# ir_circuit_rev01.net
KiCad netlist of a schematic drawn in EAGLE
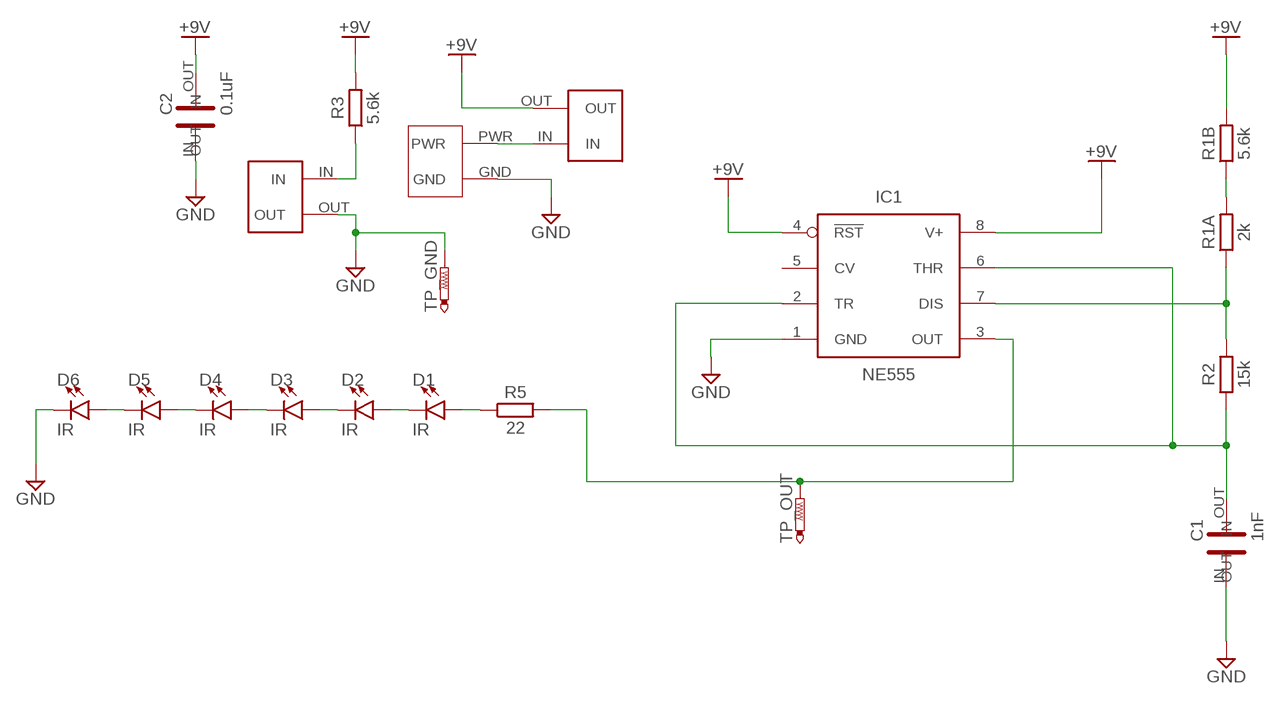
[diagram p0: schematic, sheet 1]

(export (version "E")
  (design (tool "Eeschema 10.0.6"))
  (components
    (comp (ref "BATT")
      (value "JST_THRU_HOLE")
      (footprint "eagle-import:JST_THRU_HOLE")
      (libsource (lib "eagle-import") (part "JST_THRU_HOLE"))
    )
    (comp (ref "C1")
      (value "1nF")
      (footprint "eagle-import:THRU_HOLE_CAP")
      (libsource (lib "eagle-import") (part "THRU_HOLE_CAP"))
    )
    (comp (ref "C2")
      (value "0.1uF")
      (footprint "eagle-import:THRU_HOLE_CAP")
      (libsource (lib "eagle-import") (part "THRU_HOLE_CAP"))
    )
    (comp (ref "D1")
      (value "IR")
      (footprint "eagle-import:LED_5MM")
      (libsource (lib "eagle-import") (part "LED-IRTSAL6100"))
    )
    (comp (ref "D2")
      (value "IR")
      (footprint "eagle-import:LED_5MM")
      (libsource (lib "eagle-import") (part "LED-IRTSAL6100"))
    )
    (comp (ref "D3")
      (value "IR")
      (footprint "eagle-import:LED_5MM")
      (libsource (lib "eagle-import") (part "LED-IRTSAL6100"))
    )
    (comp (ref "D4")
      (value "IR")
      (footprint "eagle-import:LED_5MM")
      (libsource (lib "eagle-import") (part "LED-IRTSAL6100"))
    )
    (comp (ref "D5")
      (value "IR")
      (footprint "eagle-import:LED_5MM")
      (libsource (lib "eagle-import") (part "LED-IRTSAL6100"))
    )
    (comp (ref "D6")
      (value "IR")
      (footprint "eagle-import:LED_5MM")
      (libsource (lib "eagle-import") (part "LED-IRTSAL6100"))
    )
    (comp (ref "IC1")
      (value "NE555")
      (footprint "eagle-import:DIP826W53P254L959H508Q8B")
      (fields
        (field (name "MANUFACTURER") "Renesas Electronics America Inc ")
        (field (name "MPN") "ICM7555IPAZ ")
      )
      (libsource (lib "eagle-import") (part "555_DIPICM7"))
    )
    (comp (ref "R1A")
      (value "2k")
      (footprint "eagle-import:RESAD1176W63L850D250B")
      (libsource (lib "eagle-import") (part "RAXIAL-11.7MM-PITCH_"))
    )
    (comp (ref "R1B")
      (value "5.6k")
      (footprint "eagle-import:RESAD1176W63L850D250B")
      (libsource (lib "eagle-import") (part "RAXIAL-11.7MM-PITCH_"))
    )
    (comp (ref "R2")
      (value "15k")
      (footprint "eagle-import:RESAD1176W63L850D250B")
      (libsource (lib "eagle-import") (part "RAXIAL-11.7MM-PITCH_"))
    )
    (comp (ref "R3")
      (value "5.6k")
      (footprint "eagle-import:RESAD1176W63L850D250B")
      (libsource (lib "eagle-import") (part "RAXIAL-11.7MM-PITCH_"))
    )
    (comp (ref "R5")
      (value "22")
      (footprint "eagle-import:RESAD1176W63L850D250B")
      (libsource (lib "eagle-import") (part "RAXIAL-11.7MM-PITCH_"))
    )
    (comp (ref "RED")
      (value "LED")
      (footprint "eagle-import:GEN_CONN")
      (libsource (lib "eagle-import") (part "GEN_CONN"))
    )
    (comp (ref "S1")
      (value "GEN_CONN")
      (footprint "eagle-import:GEN_CONN")
      (libsource (lib "eagle-import") (part "GEN_CONN"))
    )
    (comp (ref "TP_GND")
      (value "PTR1B2,54")
      (footprint "eagle-import:B2,54")
      (libsource (lib "eagle-import") (part "PTR1B2,54"))
    )
    (comp (ref "TP_OUT")
      (value "PTR1B2,54")
      (footprint "eagle-import:B2,54")
      (libsource (lib "eagle-import") (part "PTR1B2,54"))
    )
  )
  (nets
    (net (code "1") (name "+9V") (class "Default")
      (node (ref "C2") (pin "OUT") (pinfunction "OUT_OUT") (pintype "bidirectional"))
      (node (ref "IC1") (pin "4") (pinfunction "~{RST}_4") (pintype "input"))
      (node (ref "IC1") (pin "8") (pinfunction "V+_8") (pintype "power_in"))
      (node (ref "R1B") (pin "2") (pinfunction "2_2") (pintype "passive"))
      (node (ref "R3") (pin "2") (pinfunction "2_2") (pintype "passive"))
      (node (ref "S1") (pin "OUT") (pinfunction "OUT_OUT") (pintype "bidirectional"))
    )
    (net (code "2") (name "GND") (class "Default")
      (node (ref "BATT") (pin "GND") (pinfunction "GND_GND") (pintype "bidirectional"))
      (node (ref "C1") (pin "IN") (pinfunction "IN_IN") (pintype "bidirectional"))
      (node (ref "C2") (pin "IN") (pinfunction "IN_IN") (pintype "bidirectional"))
      (node (ref "D6") (pin "K") (pinfunction "C_K") (pintype "passive"))
      (node (ref "IC1") (pin "1") (pinfunction "GND_1") (pintype "power_in"))
      (node (ref "RED") (pin "OUT") (pinfunction "OUT_OUT") (pintype "bidirectional"))
      (node (ref "TP_GND") (pin "TP") (pinfunction "TP_TP") (pintype "input"))
    )
    (net (code "3") (name "Net-(BATT-PadPWR)") (class "Default")
      (node (ref "BATT") (pin "PWR") (pinfunction "PWR_PWR") (pintype "bidirectional"))
      (node (ref "S1") (pin "IN") (pinfunction "IN_IN") (pintype "bidirectional"))
    )
    (net (code "4") (name "Net-(D1-C)") (class "Default")
      (node (ref "D1") (pin "K") (pinfunction "C_K") (pintype "passive"))
      (node (ref "D2") (pin "A") (pinfunction "A_A") (pintype "passive"))
    )
    (net (code "5") (name "Net-(D1-PadA)") (class "Default")
      (node (ref "D1") (pin "A") (pinfunction "A_A") (pintype "passive"))
      (node (ref "R5") (pin "1") (pinfunction "1_1") (pintype "passive"))
    )
    (net (code "6") (name "Net-(D2-C)") (class "Default")
      (node (ref "D2") (pin "K") (pinfunction "C_K") (pintype "passive"))
      (node (ref "D3") (pin "A") (pinfunction "A_A") (pintype "passive"))
    )
    (net (code "7") (name "Net-(D3-C)") (class "Default")
      (node (ref "D3") (pin "K") (pinfunction "C_K") (pintype "passive"))
      (node (ref "D4") (pin "A") (pinfunction "A_A") (pintype "passive"))
    )
    (net (code "8") (name "Net-(D4-C)") (class "Default")
      (node (ref "D4") (pin "K") (pinfunction "C_K") (pintype "passive"))
      (node (ref "D5") (pin "A") (pinfunction "A_A") (pintype "passive"))
    )
    (net (code "9") (name "Net-(D5-C)") (class "Default")
      (node (ref "D5") (pin "K") (pinfunction "C_K") (pintype "passive"))
      (node (ref "D6") (pin "A") (pinfunction "A_A") (pintype "passive"))
    )
    (net (code "10") (name "Net-(IC1-DIS)") (class "Default")
      (node (ref "IC1") (pin "7") (pinfunction "DIS_7") (pintype "input"))
      (node (ref "R1A") (pin "1") (pinfunction "1_1") (pintype "passive"))
      (node (ref "R2") (pin "2") (pinfunction "2_2") (pintype "passive"))
    )
    (net (code "11") (name "Net-(IC1-OUT)") (class "Default")
      (node (ref "IC1") (pin "3") (pinfunction "OUT_3") (pintype "output"))
      (node (ref "R5") (pin "2") (pinfunction "2_2") (pintype "passive"))
      (node (ref "TP_OUT") (pin "TP") (pinfunction "TP_TP") (pintype "input"))
    )
    (net (code "12") (name "Net-(IC1-THR)") (class "Default")
      (node (ref "C1") (pin "OUT") (pinfunction "OUT_OUT") (pintype "bidirectional"))
      (node (ref "IC1") (pin "2") (pinfunction "TR_2") (pintype "input"))
      (node (ref "IC1") (pin "6") (pinfunction "THR_6") (pintype "input"))
      (node (ref "R2") (pin "1") (pinfunction "1_1") (pintype "passive"))
    )
    (net (code "13") (name "Net-(R1A-Pad2)") (class "Default")
      (node (ref "R1A") (pin "2") (pinfunction "2_2") (pintype "passive"))
      (node (ref "R1B") (pin "1") (pinfunction "1_1") (pintype "passive"))
    )
    (net (code "14") (name "Net-(R3-Pad1)") (class "Default")
      (node (ref "R3") (pin "1") (pinfunction "1_1") (pintype "passive"))
      (node (ref "RED") (pin "IN") (pinfunction "IN_IN") (pintype "bidirectional"))
    )
    (net (code "15") (name "unconnected-(IC1-CV-Pad5)") (class "Default")
      (node (ref "IC1") (pin "5") (pinfunction "CV_5") (pintype "input"))
    )
  )
)
